# rev02_7.net
KiCad netlist of a schematic drawn in Altium Designer
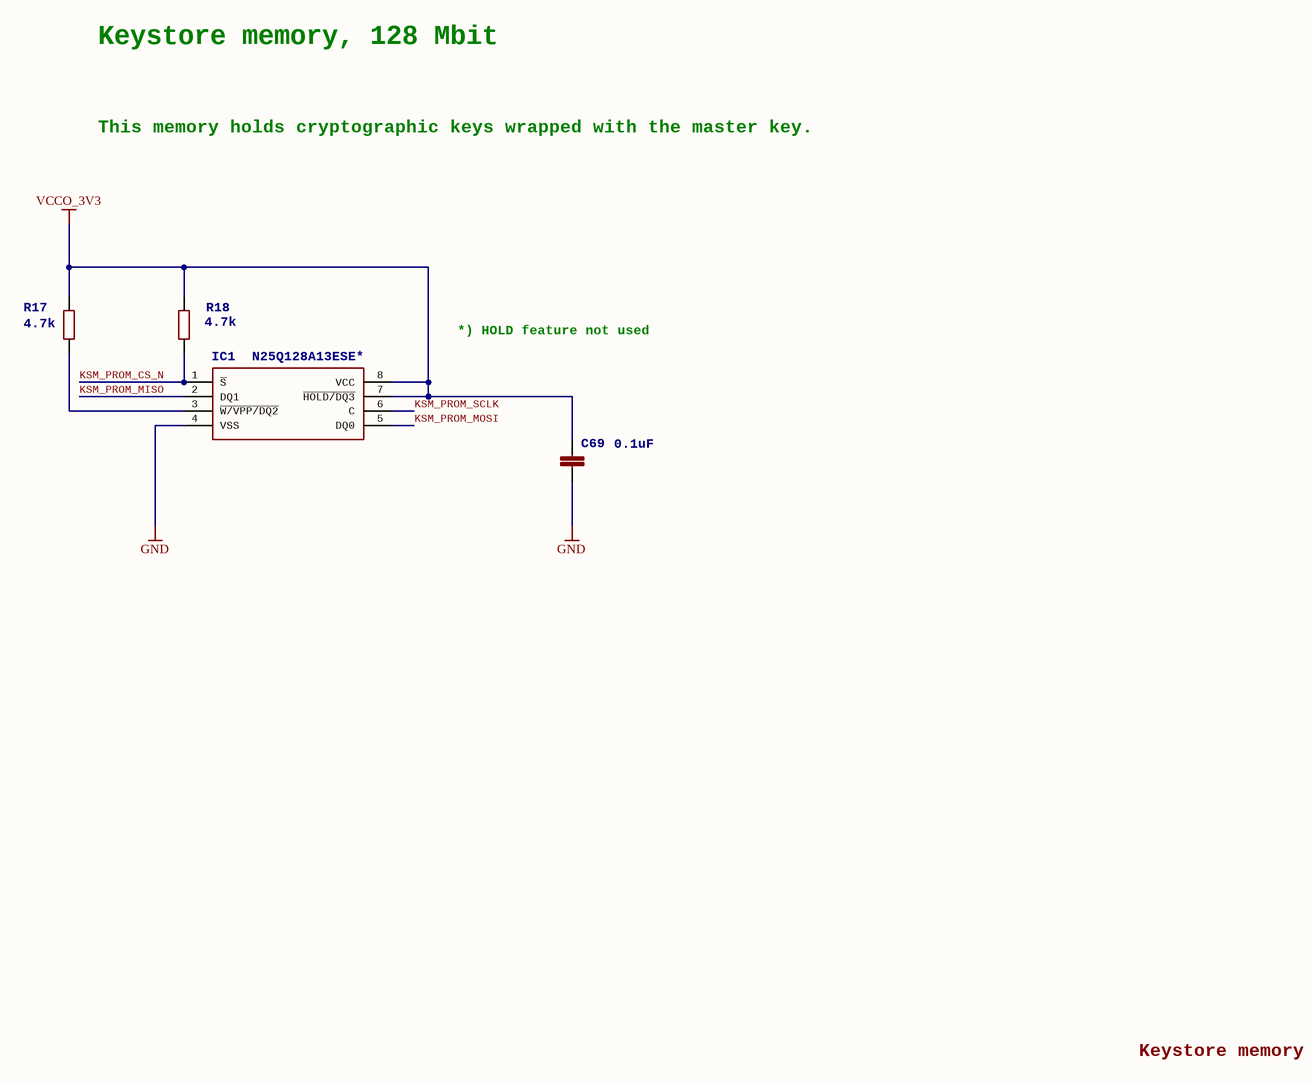
[diagram p0: rev02_7.SchDoc]

(export (version "E")
  (design (tool "Eeschema 10.0.6"))
  (components
    (comp (ref "C69")
      (value "0.1uF")
      (footprint "C_0402")
      (description "0402 CAPACITOR")
      (fields (field (name "TOLERANCE") "10%") (field (name ">NAME") "C69"))
      (libsource (lib "resistor") (part "C-EUC0402"))
    )
    (comp (ref "IC1")
      (value "N25Q128A13ESE*")
      (footprint "SO08")
      (description "NOR Flash")
      (fields (field (name ">NAME") "IC1"))
      (libsource (lib "altera-configdevices") (part "N25Q128A13ES"))
    )
    (comp (ref "R17")
      (value "4.7k")
      (footprint "R_0402")
      (description "0402 Resistor 5%")
      (libsource (lib "resistor") (part "R-EU_R0402"))
    )
    (comp (ref "R18")
      (value "4.7k")
      (footprint "R_0402")
      (description "0402 Resistor 5%")
      (libsource (lib "resistor") (part "R-EU_R0402"))
    )
  )
  (nets
    (net (code "1") (name "/KSM_PROM_CS_N") (class "Default")
      (node (ref "IC1") (pin "1") (pinfunction "~{S}_1") (pintype "passive"))
      (node (ref "R18") (pin "2") (pinfunction "2_2") (pintype "passive"))
    )
    (net (code "2") (name "/KSM_PROM_MISO") (class "Default")
      (node (ref "IC1") (pin "2") (pinfunction "DQ1_2") (pintype "passive"))
    )
    (net (code "3") (name "/KSM_PROM_MOSI") (class "Default")
      (node (ref "IC1") (pin "5") (pinfunction "DQ0_5") (pintype "passive"))
    )
    (net (code "4") (name "/KSM_PROM_SCLK") (class "Default")
      (node (ref "IC1") (pin "6") (pinfunction "C_6") (pintype "passive"))
    )
    (net (code "5") (name "GND") (class "Default")
      (node (ref "C69") (pin "2") (pinfunction "2_2") (pintype "passive"))
      (node (ref "IC1") (pin "4") (pinfunction "VSS_4") (pintype "passive"))
    )
    (net (code "6") (name "Net-(IC1-~{W{slash}VPP{slash}DQ2})") (class "Default")
      (node (ref "IC1") (pin "3") (pinfunction "~{W/VPP/DQ2}_3") (pintype "passive"))
      (node (ref "R17") (pin "2") (pinfunction "2_2") (pintype "passive"))
    )
    (net (code "7") (name "VCCO_3V3") (class "Default")
      (node (ref "C69") (pin "1") (pinfunction "1_1") (pintype "passive"))
      (node (ref "IC1") (pin "7") (pinfunction "~{HOLD/DQ3}_7") (pintype "passive"))
      (node (ref "IC1") (pin "8") (pinfunction "VCC_8") (pintype "passive"))
      (node (ref "R17") (pin "1") (pinfunction "1_1") (pintype "passive"))
      (node (ref "R18") (pin "1") (pinfunction "1_1") (pintype "passive"))
    )
  )
)
